# SCH_NFC_BUSINESS_CARD_2023-09-29.net
KiCad netlist of a schematic drawn in EasyEDA
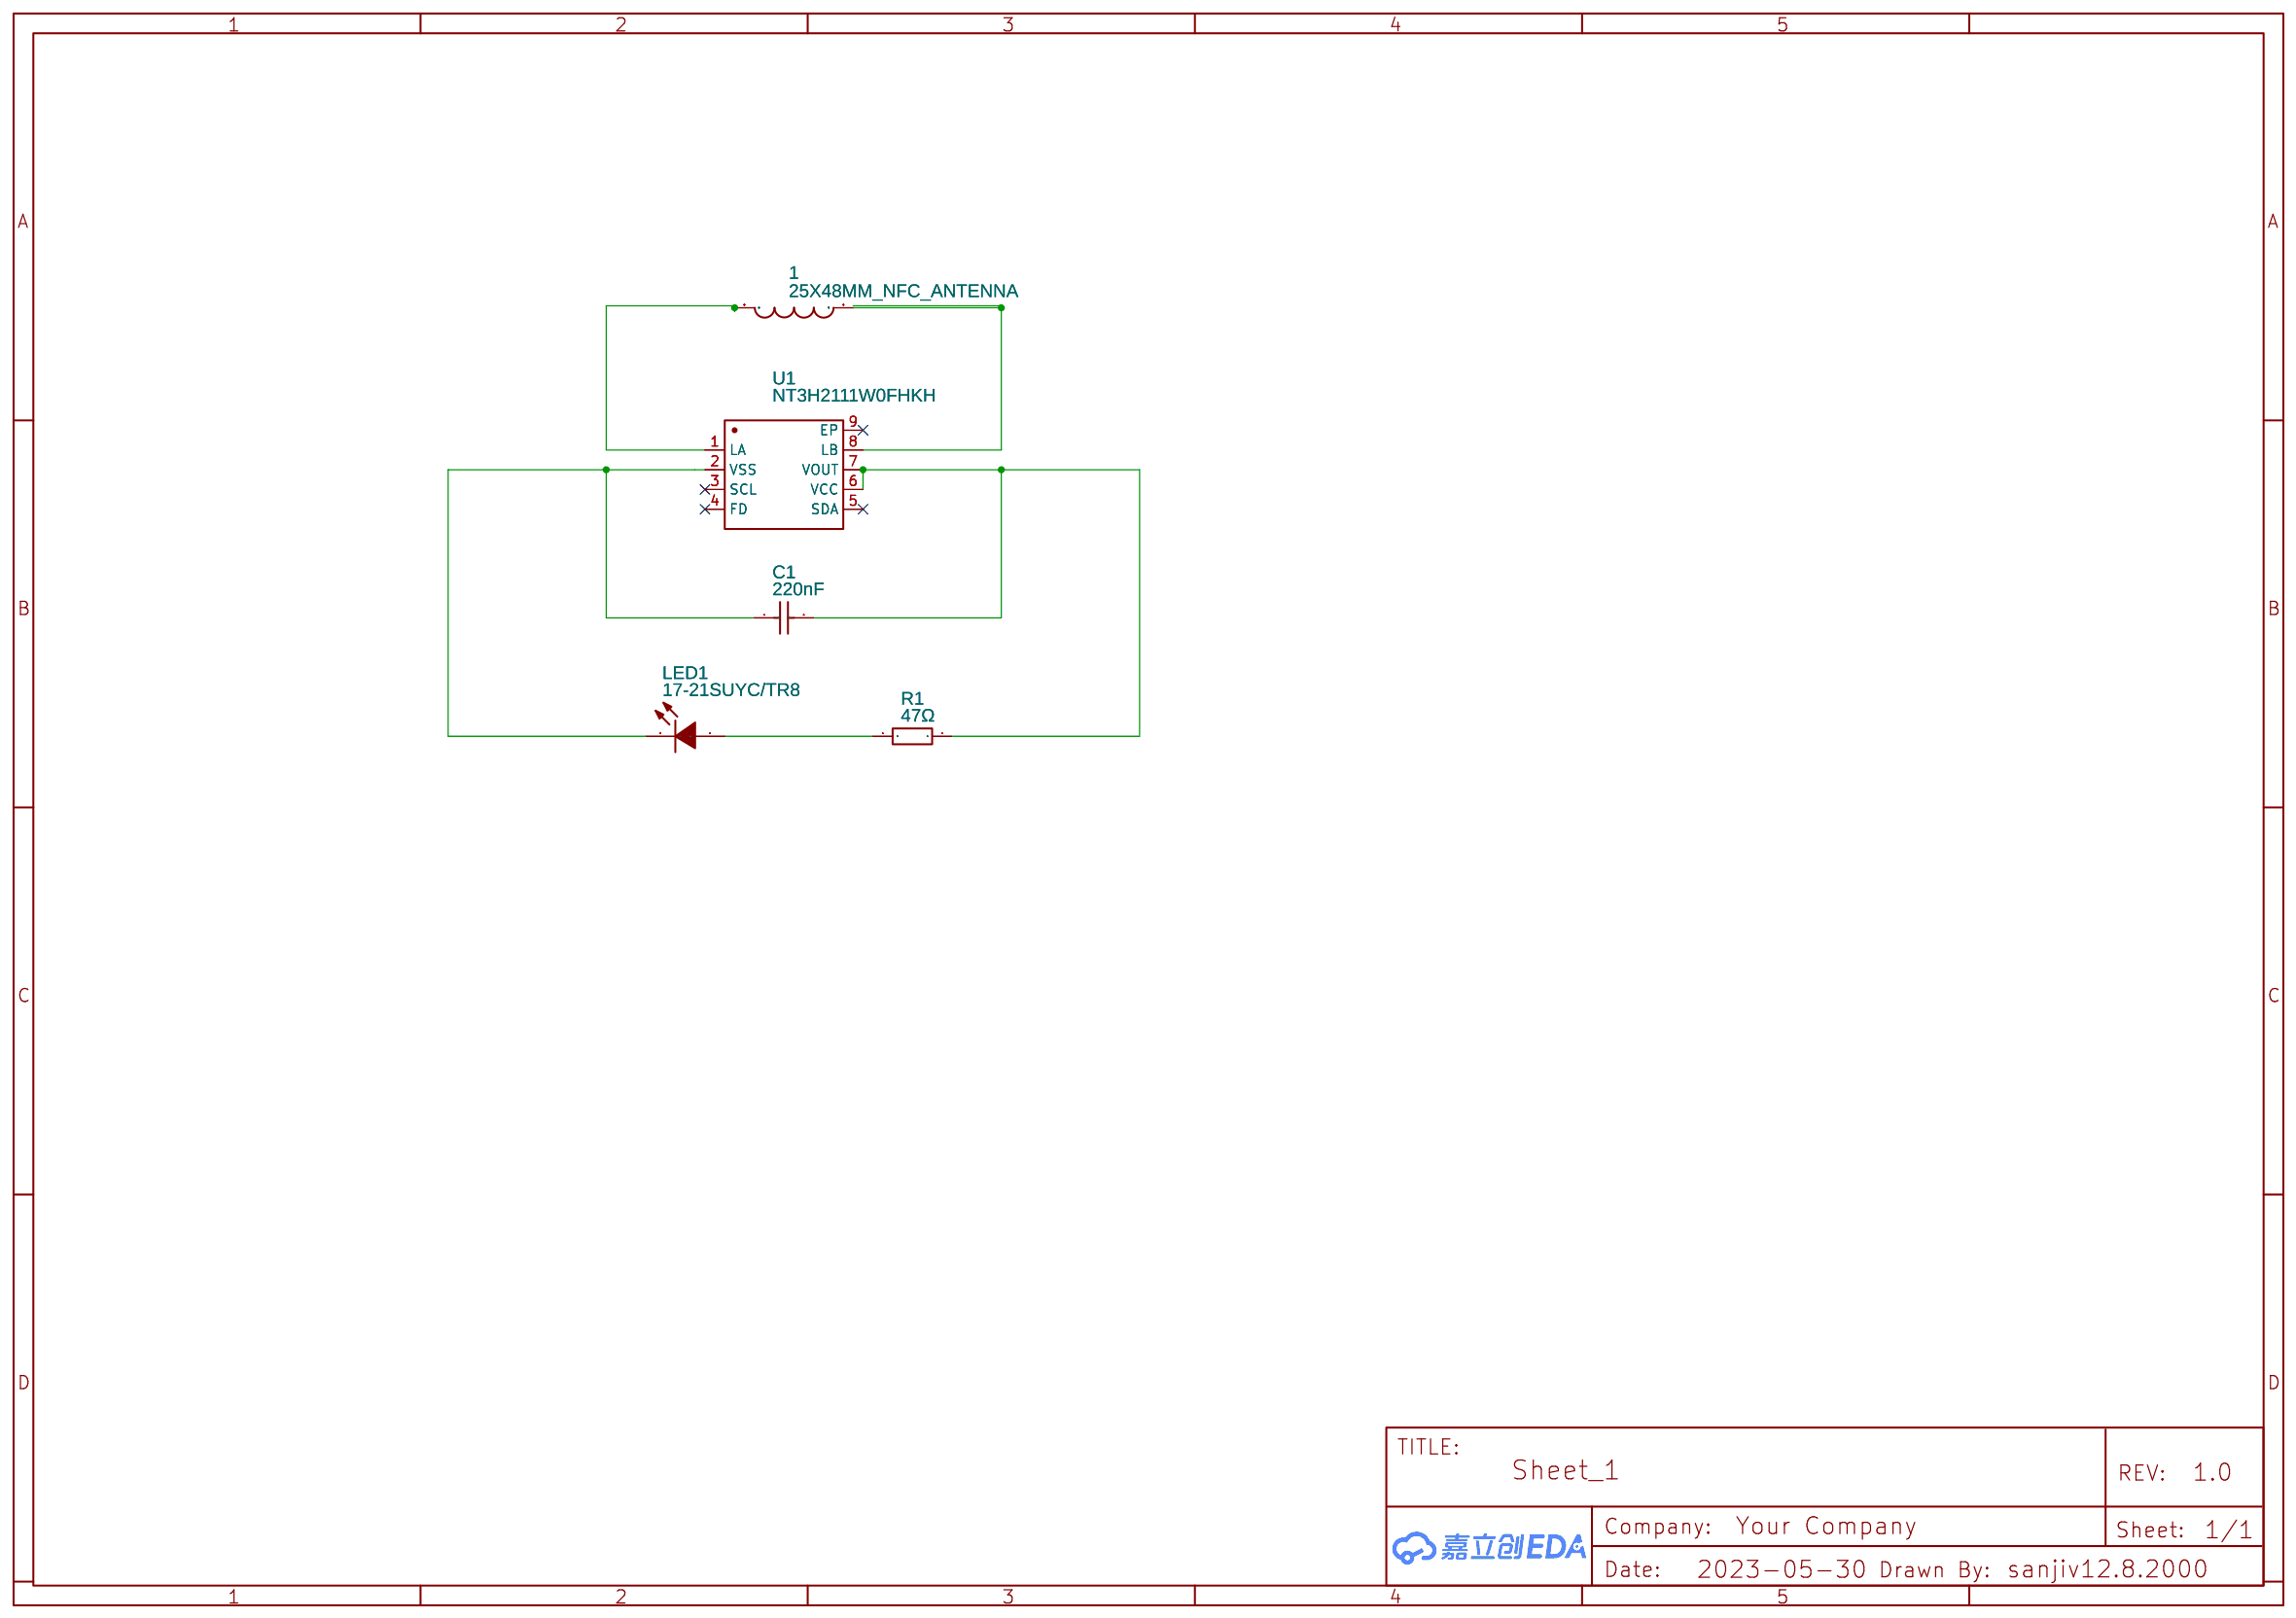
[diagram p0: schematic sheet]

(export (version "E")
  (design (tool "Eeschema 10.0.6"))
  (components
    (comp (ref "1") (value "25X48MM_NFC_ANTENNA") (libsource (lib "") (part "25X48MM_NFC_ANTENNA")))
    (comp (ref "C1")
      (value "220nF")
      (fields
        (field (name "Manufacturer Part") "CL10B224KA8NNNC")
        (field (name "Manufacturer") "SAMSUNG(三星)")
      )
      (libsource (lib "") (part "CL10B224KA8NNNC"))
    )
    (comp (ref "LED1")
      (value "17-21SUYC/TR8")
      (fields (field (name "Manufacturer Part") "KT-0805黄灯") (field (name "Manufacturer") "KENTO"))
      (libsource (lib "") (part "17-21SUYC/TR8"))
    )
    (comp (ref "R1")
      (value "47Ω")
      (fields
        (field (name "Manufacturer Part") "0603WAF470JT5E")
        (field (name "Manufacturer") "UNI-ROYAL(厚声)")
      )
      (libsource (lib "") (part "0603WAF470JT5E"))
    )
    (comp (ref "U1")
      (value "NT3H2111W0FHKH")
      (fields (field (name "Manufacturer") "NXP(恩智浦)"))
      (libsource (lib "") (part "NT3H2111W0FHKH"))
    )
  )
  (nets
    (net (code "1") (name "Net-(LED1-+)") (class "Default")
      (node (ref "LED1") (pin "1") (pinfunction "+_1") (pintype "unspecified"))
      (node (ref "R1") (pin "1") (pinfunction "1_1") (pintype "input"))
    )
    (net (code "2") (name "Net-(LED1--)") (class "Default")
      (node (ref "C1") (pin "1") (pinfunction "1_1") (pintype "input"))
      (node (ref "LED1") (pin "2") (pinfunction "-_2") (pintype "unspecified"))
      (node (ref "U1") (pin "2") (pinfunction "VSS_2") (pintype "unspecified"))
    )
    (net (code "3") (name "Net-(U1-LA)") (class "Default")
      (node (ref "1") (pin "P$2") (pinfunction "P$2_P$2") (pintype "bidirectional"))
      (node (ref "U1") (pin "1") (pinfunction "LA_1") (pintype "unspecified"))
    )
    (net (code "4") (name "Net-(U1-LB)") (class "Default")
      (node (ref "1") (pin "P$1") (pinfunction "P$1_P$1") (pintype "bidirectional"))
      (node (ref "U1") (pin "8") (pinfunction "LB_8") (pintype "unspecified"))
    )
    (net (code "5") (name "Net-(U1-VCC)") (class "Default")
      (node (ref "C1") (pin "2") (pinfunction "2_2") (pintype "input"))
      (node (ref "R1") (pin "2") (pinfunction "2_2") (pintype "input"))
      (node (ref "U1") (pin "6") (pinfunction "VCC_6") (pintype "unspecified"))
      (node (ref "U1") (pin "7") (pinfunction "VOUT_7") (pintype "unspecified"))
    )
    (net (code "6") (name "unconnected-(U1-EP-Pad9)") (class "Default")
      (node (ref "U1") (pin "9") (pinfunction "EP_9") (pintype "unspecified+no_connect"))
    )
    (net (code "7") (name "unconnected-(U1-FD-Pad4)") (class "Default")
      (node (ref "U1") (pin "4") (pinfunction "FD_4") (pintype "unspecified+no_connect"))
    )
    (net (code "8") (name "unconnected-(U1-SCL-Pad3)") (class "Default")
      (node (ref "U1") (pin "3") (pinfunction "SCL_3") (pintype "unspecified+no_connect"))
    )
    (net (code "9") (name "unconnected-(U1-SDA-Pad5)") (class "Default")
      (node (ref "U1") (pin "5") (pinfunction "SDA_5") (pintype "unspecified+no_connect"))
    )
  )
)
